# interface.net
KiCad netlist of a schematic drawn in EAGLE
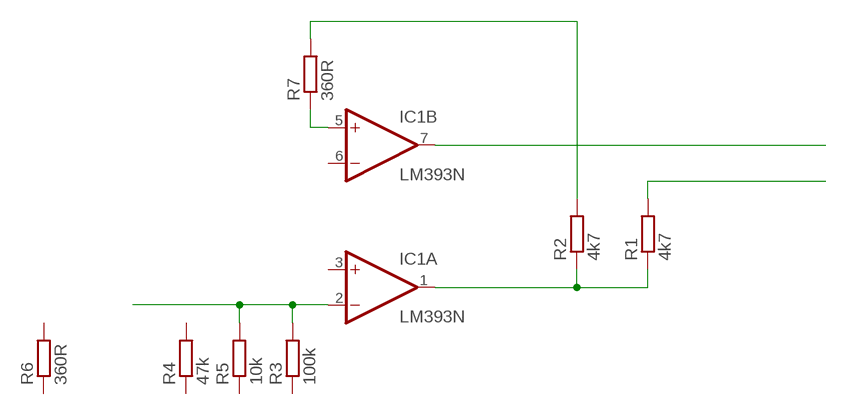
[diagram p0: schematic, sheet 1]

(export (version "E")
  (design (tool "Eeschema 10.0.6"))
  (components
    (comp (ref "IC1")
      (value "LM393N")
      (footprint "eagle-import:DIL08")
      (libsource (lib "eagle-import") (part "LM393N"))
    )
    (comp (ref "R1")
      (value "4k7")
      (footprint "eagle-import:R0805")
      (libsource (lib "eagle-import") (part "R-EU_R0805"))
    )
    (comp (ref "R2")
      (value "4k7")
      (footprint "eagle-import:R0805")
      (libsource (lib "eagle-import") (part "R-EU_R0805"))
    )
    (comp (ref "R3")
      (value "100k")
      (footprint "eagle-import:R0805")
      (libsource (lib "eagle-import") (part "R-EU_R0805"))
    )
    (comp (ref "R4")
      (value "47k")
      (footprint "eagle-import:R0805")
      (libsource (lib "eagle-import") (part "R-EU_R0805"))
    )
    (comp (ref "R5")
      (value "10k")
      (footprint "eagle-import:R0805")
      (libsource (lib "eagle-import") (part "R-EU_R0805"))
    )
    (comp (ref "R6")
      (value "360R")
      (footprint "eagle-import:R0805")
      (libsource (lib "eagle-import") (part "R-EU_R0805"))
    )
    (comp (ref "R7")
      (value "360R")
      (footprint "eagle-import:R0805")
      (libsource (lib "eagle-import") (part "R-EU_R0805"))
    )
  )
  (nets
    (net (code "1") (name "Net-(IC1A--IN)") (class "Default")
      (node (ref "IC1") (pin "2") (pinfunction "-IN_2") (pintype "input"))
      (node (ref "R3") (pin "2") (pinfunction "2_2") (pintype "passive"))
      (node (ref "R5") (pin "2") (pinfunction "2_2") (pintype "passive"))
    )
    (net (code "2") (name "Net-(IC1A-OUT)") (class "Default")
      (node (ref "IC1") (pin "1") (pinfunction "OUT_1") (pintype "output"))
      (node (ref "R1") (pin "1") (pinfunction "1_1") (pintype "passive"))
      (node (ref "R2") (pin "1") (pinfunction "1_1") (pintype "passive"))
    )
    (net (code "3") (name "Net-(IC1B-+IN)") (class "Default")
      (node (ref "IC1") (pin "5") (pinfunction "+IN_5") (pintype "input"))
      (node (ref "R7") (pin "1") (pinfunction "1_1") (pintype "passive"))
    )
    (net (code "4") (name "Net-(R2-Pad2)") (class "Default")
      (node (ref "R2") (pin "2") (pinfunction "2_2") (pintype "passive"))
      (node (ref "R7") (pin "2") (pinfunction "2_2") (pintype "passive"))
    )
    (net (code "5") (name "unconnected-(IC1A-+IN-Pad3)") (class "Default")
      (node (ref "IC1") (pin "3") (pinfunction "+IN_3") (pintype "input"))
    )
    (net (code "6") (name "unconnected-(IC1B--IN-Pad6)") (class "Default")
      (node (ref "IC1") (pin "6") (pinfunction "-IN_6") (pintype "input"))
    )
    (net (code "7") (name "unconnected-(IC1B-OUT-Pad7)") (class "Default")
      (node (ref "IC1") (pin "7") (pinfunction "OUT_7") (pintype "output"))
    )
    (net (code "8") (name "unconnected-(R1-Pad2)") (class "Default")
      (node (ref "R1") (pin "2") (pinfunction "2_2") (pintype "passive"))
    )
    (net (code "9") (name "unconnected-(R3-Pad1)") (class "Default")
      (node (ref "R3") (pin "1") (pinfunction "1_1") (pintype "passive"))
    )
    (net (code "10") (name "unconnected-(R4-Pad1)") (class "Default")
      (node (ref "R4") (pin "1") (pinfunction "1_1") (pintype "passive"))
    )
    (net (code "11") (name "unconnected-(R4-Pad2)") (class "Default")
      (node (ref "R4") (pin "2") (pinfunction "2_2") (pintype "passive"))
    )
    (net (code "12") (name "unconnected-(R5-Pad1)") (class "Default")
      (node (ref "R5") (pin "1") (pinfunction "1_1") (pintype "passive"))
    )
    (net (code "13") (name "unconnected-(R6-Pad1)") (class "Default")
      (node (ref "R6") (pin "1") (pinfunction "1_1") (pintype "passive"))
    )
    (net (code "14") (name "unconnected-(R6-Pad2)") (class "Default")
      (node (ref "R6") (pin "2") (pinfunction "2_2") (pintype "passive"))
    )
  )
)
